# Connectors.net
KiCad netlist of a schematic drawn in Altium Designer
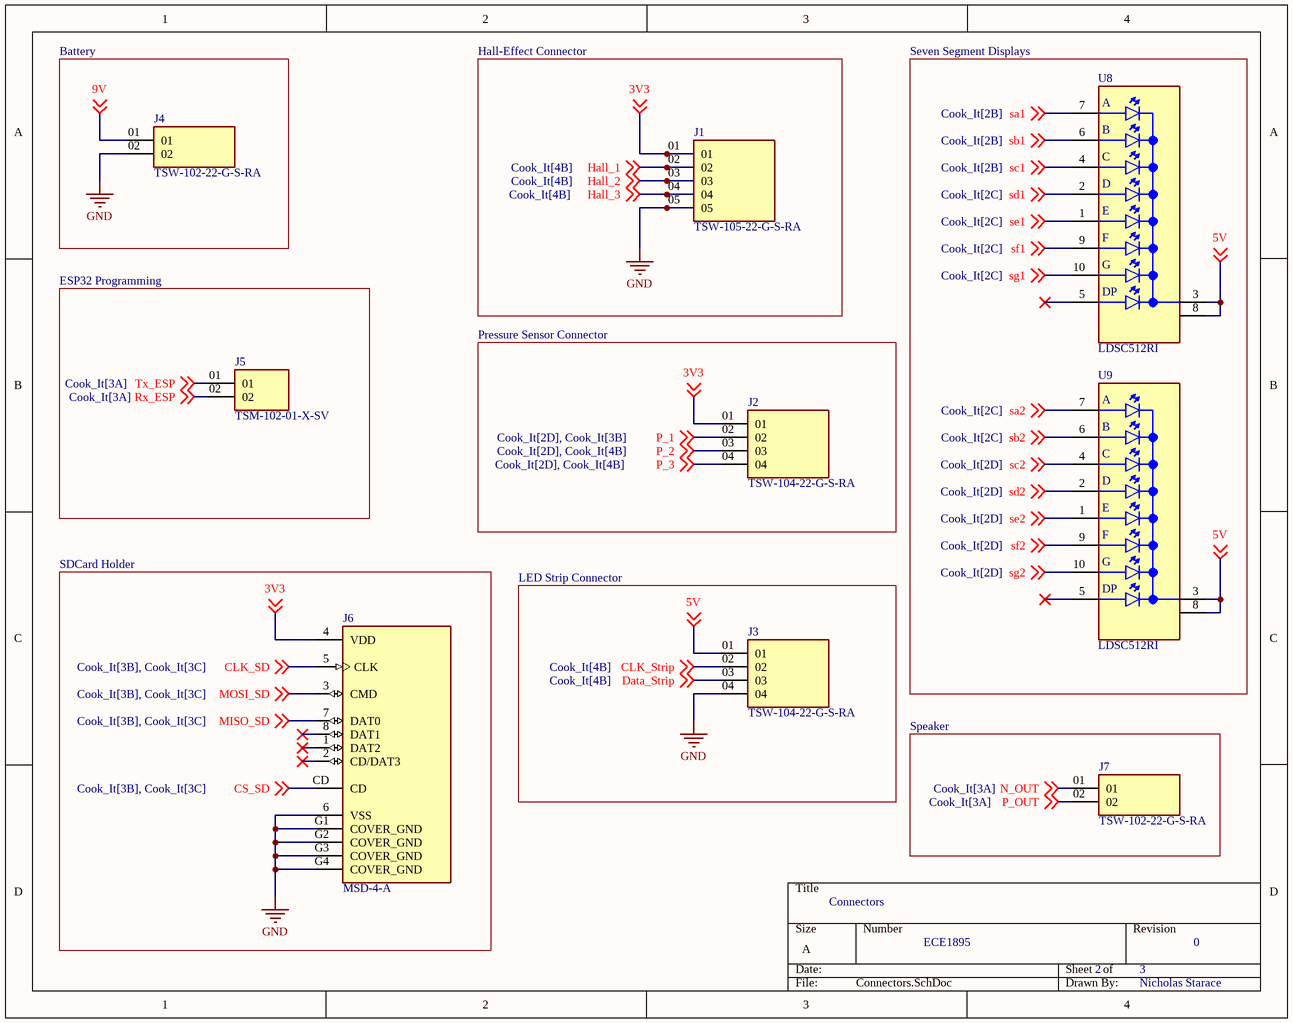
[diagram p0: Connectors.SchDoc]

(export (version "E")
  (design (tool "Eeschema 10.0.6"))
  (components
    (comp (ref "J1")
      (value "TSW-105-22-G-S-RA")
      (footprint "SAMTEC_TSW-105-22-G-S-RA")
      (description "Conn Unshrouded Header HDR 5 POS 2.54mm Solder RA Side Entry Thru-Hole Bulk")
      (fields (field (name "MF") "Samtec"))
      (libsource (lib "TSW-105-22-G-S-RA") (part "TSW-105-22-G-S-RA"))
    )
    (comp (ref "J2")
      (value "TSW-104-22-G-S-RA")
      (footprint "SAMTEC_TSW-104-22-G-S-RA")
      (fields (field (name "MF") "Samtec"))
      (libsource (lib "TSW-104-22-G-S-RA") (part "TSW-104-22-G-S-RA"))
    )
    (comp (ref "J3")
      (value "TSW-104-22-G-S-RA")
      (footprint "SAMTEC_TSW-104-22-G-S-RA")
      (fields (field (name "MF") "Samtec"))
      (libsource (lib "TSW-104-22-G-S-RA") (part "TSW-104-22-G-S-RA"))
    )
    (comp (ref "J4")
      (value "TSW-102-22-G-S-RA")
      (footprint "SAMTEC_TSW-102-22-G-S-RA")
      (fields (field (name "MF") "Samtec"))
      (libsource (lib "TSW-102-22-G-S-RA") (part "TSW-102-22-G-S-RA"))
    )
    (comp (ref "J5")
      (value "TSM-102-01-X-SV")
      (footprint "SAMTEC_TSM-102-01-X-SV")
      (description "TSM - Samtec 2.54mm Single Row Vertical Surface Mount Header 5.84mm Post Height (01) - Fast Stock")
      (fields (field (name "MF") "Samtec") (field (name "MP") "TSM-102-01-L-SV"))
      (libsource (lib "TSM-102-01-X-SV") (part "TSM-102-01-X-SV"))
    )
    (comp (ref "J6")
      (value "MSD-4-A")
      (footprint "CUI_MSD-4-A")
      (fields (field (name "MF") "Same Sky"))
      (libsource (lib "MSD-4-A") (part "MSD-4-A"))
    )
    (comp (ref "J7")
      (value "TSW-102-22-G-S-RA")
      (footprint "SAMTEC_TSW-102-22-G-S-RA")
      (fields (field (name "MF") "Samtec"))
      (libsource (lib "TSW-102-22-G-S-RA") (part "TSW-102-22-G-S-RA"))
    )
    (comp (ref "U8")
      (value "LDSC512RI")
      (footprint "LED_LDSC512RI")
      (description ".56IN. 7 SEGMENT SINGLE DISPLAY, 565NM GREEN, GRAY FACE, WHITE SEGMENTS, COMMON ¦ Lumex LDS-C512RI")
      (fields (field (name "MF") "Lumex") (field (name "MP") "LDS-C512RI"))
      (libsource (lib "LDSC512RI") (part "LDSC512RI"))
    )
    (comp (ref "U9")
      (value "LDSC512RI")
      (footprint "LED_LDSC512RI")
      (description ".56IN. 7 SEGMENT SINGLE DISPLAY, 565NM GREEN, GRAY FACE, WHITE SEGMENTS, COMMON ¦ Lumex LDS-C512RI")
      (fields (field (name "MF") "Lumex") (field (name "MP") "LDS-C512RI"))
      (libsource (lib "LDSC512RI") (part "LDSC512RI"))
    )
  )
  (nets
    (net (code "1") (name "3V3") (class "Default")
      (node (ref "J1") (pin "01") (pinfunction "01_01") (pintype "passive"))
      (node (ref "J2") (pin "01") (pinfunction "01_01") (pintype "passive"))
      (node (ref "J6") (pin "4") (pinfunction "VDD_4") (pintype "power_in"))
    )
    (net (code "2") (name "5V") (class "Default")
      (node (ref "J3") (pin "01") (pinfunction "01_01") (pintype "passive"))
      (node (ref "U8") (pin "3") (pinfunction "CC_3") (pintype "passive"))
      (node (ref "U8") (pin "8") (pinfunction "CC_8") (pintype "passive"))
      (node (ref "U9") (pin "3") (pinfunction "CC_3") (pintype "passive"))
      (node (ref "U9") (pin "8") (pinfunction "CC_8") (pintype "passive"))
    )
    (net (code "3") (name "9V") (class "Default")
      (node (ref "J4") (pin "01") (pinfunction "01_01") (pintype "passive"))
    )
    (net (code "4") (name "CLK_SD") (class "Default")
      (node (ref "J6") (pin "5") (pinfunction "CLK_5") (pintype "input"))
    )
    (net (code "5") (name "CLK_Strip") (class "Default")
      (node (ref "J3") (pin "02") (pinfunction "02_02") (pintype "passive"))
    )
    (net (code "6") (name "CS_SD") (class "Default")
      (node (ref "J6") (pin "CD") (pinfunction "CD_CD") (pintype "passive"))
    )
    (net (code "7") (name "Data_Strip") (class "Default")
      (node (ref "J3") (pin "03") (pinfunction "03_03") (pintype "passive"))
    )
    (net (code "8") (name "GND") (class "Default")
      (node (ref "J1") (pin "05") (pinfunction "05_05") (pintype "passive"))
      (node (ref "J3") (pin "04") (pinfunction "04_04") (pintype "passive"))
      (node (ref "J4") (pin "02") (pinfunction "02_02") (pintype "passive"))
      (node (ref "J6") (pin "6") (pinfunction "VSS_6") (pintype "power_in"))
      (node (ref "J6") (pin "G1") (pinfunction "COVER_GND_G1") (pintype "power_in"))
      (node (ref "J6") (pin "G2") (pinfunction "COVER_GND_G2") (pintype "power_in"))
      (node (ref "J6") (pin "G3") (pinfunction "COVER_GND_G3") (pintype "power_in"))
      (node (ref "J6") (pin "G4") (pinfunction "COVER_GND_G4") (pintype "power_in"))
    )
    (net (code "9") (name "Hall_1") (class "Default")
      (node (ref "J1") (pin "02") (pinfunction "02_02") (pintype "passive"))
    )
    (net (code "10") (name "Hall_2") (class "Default")
      (node (ref "J1") (pin "03") (pinfunction "03_03") (pintype "passive"))
    )
    (net (code "11") (name "Hall_3") (class "Default")
      (node (ref "J1") (pin "04") (pinfunction "04_04") (pintype "passive"))
    )
    (net (code "12") (name "MISO_SD") (class "Default")
      (node (ref "J6") (pin "7") (pinfunction "DAT0_7") (pintype "bidirectional"))
    )
    (net (code "13") (name "MOSI_SD") (class "Default")
      (node (ref "J6") (pin "3") (pinfunction "CMD_3") (pintype "bidirectional"))
    )
    (net (code "14") (name "N_OUT") (class "Default")
      (node (ref "J7") (pin "01") (pinfunction "01_01") (pintype "passive"))
    )
    (net (code "15") (name "P_1") (class "Default")
      (node (ref "J2") (pin "02") (pinfunction "02_02") (pintype "passive"))
    )
    (net (code "16") (name "P_2") (class "Default")
      (node (ref "J2") (pin "03") (pinfunction "03_03") (pintype "passive"))
    )
    (net (code "17") (name "P_3") (class "Default")
      (node (ref "J2") (pin "04") (pinfunction "04_04") (pintype "passive"))
    )
    (net (code "18") (name "P_OUT") (class "Default")
      (node (ref "J7") (pin "02") (pinfunction "02_02") (pintype "passive"))
    )
    (net (code "19") (name "Rx_ESP") (class "Default")
      (node (ref "J5") (pin "02") (pinfunction "02_02") (pintype "passive"))
    )
    (net (code "20") (name "Tx_ESP") (class "Default")
      (node (ref "J5") (pin "01") (pinfunction "01_01") (pintype "passive"))
    )
    (net (code "21") (name "sa1") (class "Default")
      (node (ref "U8") (pin "7") (pinfunction "A_7") (pintype "passive"))
    )
    (net (code "22") (name "sa2") (class "Default")
      (node (ref "U9") (pin "7") (pinfunction "A_7") (pintype "passive"))
    )
    (net (code "23") (name "sb1") (class "Default")
      (node (ref "U8") (pin "6") (pinfunction "B_6") (pintype "passive"))
    )
    (net (code "24") (name "sb2") (class "Default")
      (node (ref "U9") (pin "6") (pinfunction "B_6") (pintype "passive"))
    )
    (net (code "25") (name "sc1") (class "Default")
      (node (ref "U8") (pin "4") (pinfunction "C_4") (pintype "passive"))
    )
    (net (code "26") (name "sc2") (class "Default")
      (node (ref "U9") (pin "4") (pinfunction "C_4") (pintype "passive"))
    )
    (net (code "27") (name "sd1") (class "Default")
      (node (ref "U8") (pin "2") (pinfunction "D_2") (pintype "passive"))
    )
    (net (code "28") (name "sd2") (class "Default")
      (node (ref "U9") (pin "2") (pinfunction "D_2") (pintype "passive"))
    )
    (net (code "29") (name "se1") (class "Default")
      (node (ref "U8") (pin "1") (pinfunction "E_1") (pintype "passive"))
    )
    (net (code "30") (name "se2") (class "Default")
      (node (ref "U9") (pin "1") (pinfunction "E_1") (pintype "passive"))
    )
    (net (code "31") (name "sf1") (class "Default")
      (node (ref "U8") (pin "9") (pinfunction "F_9") (pintype "passive"))
    )
    (net (code "32") (name "sf2") (class "Default")
      (node (ref "U9") (pin "9") (pinfunction "F_9") (pintype "passive"))
    )
    (net (code "33") (name "sg1") (class "Default")
      (node (ref "U8") (pin "10") (pinfunction "G_10") (pintype "passive"))
    )
    (net (code "34") (name "sg2") (class "Default")
      (node (ref "U9") (pin "10") (pinfunction "G_10") (pintype "passive"))
    )
    (net (code "35") (name "unconnected-(J6-CD{slash}DAT3-Pad2)") (class "Default")
      (node (ref "J6") (pin "2") (pinfunction "CD/DAT3_2") (pintype "bidirectional+no_connect"))
    )
    (net (code "36") (name "unconnected-(J6-DAT1-Pad8)") (class "Default")
      (node (ref "J6") (pin "8") (pinfunction "DAT1_8") (pintype "bidirectional+no_connect"))
    )
    (net (code "37") (name "unconnected-(J6-DAT2-Pad1)") (class "Default")
      (node (ref "J6") (pin "1") (pinfunction "DAT2_1") (pintype "bidirectional+no_connect"))
    )
    (net (code "38") (name "unconnected-(U8-DP-Pad5)") (class "Default")
      (node (ref "U8") (pin "5") (pinfunction "DP_5") (pintype "passive+no_connect"))
    )
    (net (code "39") (name "unconnected-(U9-DP-Pad5)") (class "Default")
      (node (ref "U9") (pin "5") (pinfunction "DP_5") (pintype "passive+no_connect"))
    )
  )
)
